# POWER_SUPPLY_CURVE_TRACER_V14.net
KiCad netlist of a schematic drawn in EAGLE
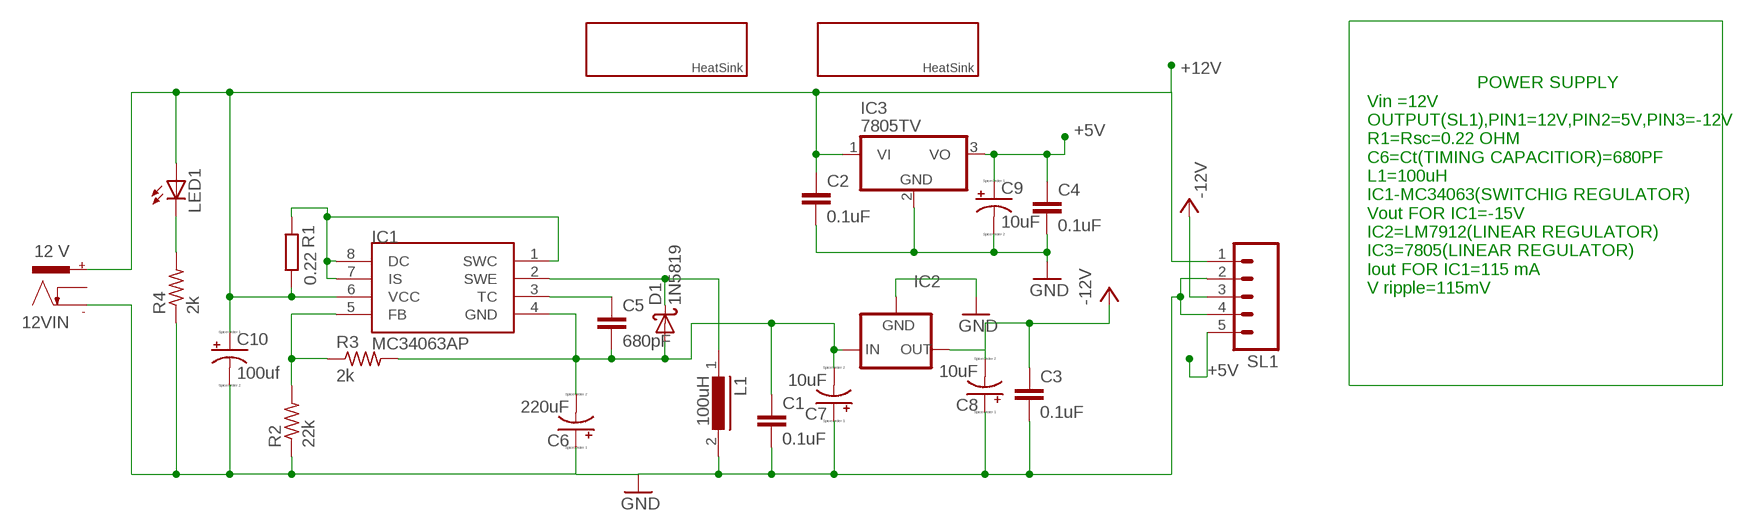
[diagram p0: schematic, sheet 1]

(export (version "E")
  (design (tool "Eeschema 10.0.6"))
  (components
    (comp (ref "12VIN")
      (value "12 V")
      (footprint "eagle-import:NEB21R")
      (libsource (lib "eagle-import") (part "POWER_CON"))
    )
    (comp (ref "C1")
      (value "0.1uF")
      (footprint "eagle-import:C025-025X050")
      (libsource (lib "eagle-import") (part "C-EU025-025X050"))
    )
    (comp (ref "C2")
      (value "0.1uF")
      (footprint "eagle-import:C025-025X050")
      (libsource (lib "eagle-import") (part "C-EU025-025X050"))
    )
    (comp (ref "C3")
      (value "0.1uF")
      (footprint "eagle-import:C025-025X050")
      (libsource (lib "eagle-import") (part "C-EU025-025X050"))
    )
    (comp (ref "C4")
      (value "0.1uF")
      (footprint "eagle-import:C025-025X050")
      (libsource (lib "eagle-import") (part "C-EU025-025X050"))
    )
    (comp (ref "C5")
      (value "680pF")
      (footprint "eagle-import:C025-025X050")
      (libsource (lib "eagle-import") (part "C-EU025-025X050"))
    )
    (comp (ref "C6")
      (value "220uF")
      (footprint "eagle-import:E2,5-7")
      (libsource (lib "eagle-import") (part "CPOL-USE2.5-7"))
    )
    (comp (ref "C7")
      (value "10uF")
      (footprint "eagle-import:E2,5-6")
      (libsource (lib "eagle-import") (part "CPOL-USE2.5-6"))
    )
    (comp (ref "C8")
      (value "10uF")
      (footprint "eagle-import:E2,5-6")
      (libsource (lib "eagle-import") (part "CPOL-USE2.5-6"))
    )
    (comp (ref "C9")
      (value "10uF")
      (footprint "eagle-import:E2,5-6")
      (libsource (lib "eagle-import") (part "CPOL-USE2.5-6"))
    )
    (comp (ref "C10")
      (value "100uf")
      (footprint "eagle-import:E2,5-7")
      (libsource (lib "eagle-import") (part "CPOL-USE2.5-7"))
    )
    (comp (ref "D1")
      (value "1N5819")
      (footprint "eagle-import:DO41-10")
      (libsource (lib "eagle-import") (part "1N5819"))
    )
    (comp (ref "IC1")
      (value "MC34063AP")
      (footprint "eagle-import:DIL08")
      (libsource (lib "eagle-import") (part "MC34063AP"))
    )
    (comp (ref "IC2")
      (value "79XXS")
      (footprint "eagle-import:79XXS")
      (libsource (lib "eagle-import") (part "79XXS"))
    )
    (comp (ref "IC3")
      (value "7805TV")
      (footprint "eagle-import:TO220V")
      (libsource (lib "eagle-import") (part "78TV05"))
    )
    (comp (ref "L1")
      (value "100uH")
      (footprint "eagle-import:82114R")
      (libsource (lib "eagle-import") (part "82114R"))
    )
    (comp (ref "LED1")
      (value "LED3MM")
      (footprint "eagle-import:LED3MM")
      (libsource (lib "eagle-import") (part "LED3MM"))
    )
    (comp (ref "R1")
      (value "0.22")
      (footprint "eagle-import:0617_17")
      (libsource (lib "eagle-import") (part "R-EU_0617/17"))
    )
    (comp (ref "R2")
      (value "22k")
      (footprint "eagle-import:0207_7")
      (libsource (lib "eagle-import") (part "RESISTOR0207/7"))
    )
    (comp (ref "R3")
      (value "2k")
      (footprint "eagle-import:0204_7")
      (libsource (lib "eagle-import") (part "R-US_0204/7"))
    )
    (comp (ref "R4")
      (value "2k")
      (footprint "eagle-import:0207_7")
      (libsource (lib "eagle-import") (part "RESISTOR0207/7"))
    )
    (comp (ref "SL1")
      (value "M05")
      (footprint "eagle-import:05P")
      (libsource (lib "eagle-import") (part "M05"))
    )
    (comp (ref "U$1")
      (value "HEATSINKMEDIUM")
      (footprint "eagle-import:HEATSINK-MED")
      (libsource (lib "eagle-import") (part "HEATSINKMEDIUM"))
    )
    (comp (ref "U$2")
      (value "HEATSINKSMALL")
      (footprint "eagle-import:HEATSINK-SML")
      (libsource (lib "eagle-import") (part "HEATSINKSMALL"))
    )
  )
  (nets
    (net (code "1") (name "-12V") (class "Default")
      (node (ref "C3") (pin "1") (pinfunction "1_1") (pintype "passive"))
      (node (ref "C8") (pin "-") (pinfunction "-_-") (pintype "passive"))
      (node (ref "IC2") (pin "OUT") (pinfunction "OUT_OUT") (pintype "passive"))
      (node (ref "SL1") (pin "3") (pinfunction "3_3") (pintype "passive"))
    )
    (net (code "2") (name "/+5V") (class "Default")
      (node (ref "C4") (pin "1") (pinfunction "1_1") (pintype "passive"))
      (node (ref "C9") (pin "+") (pinfunction "+_+") (pintype "passive"))
      (node (ref "IC3") (pin "3") (pinfunction "VO_3") (pintype "passive"))
      (node (ref "SL1") (pin "5") (pinfunction "5_5") (pintype "passive"))
    )
    (net (code "3") (name "/+12V") (class "Default")
      (node (ref "12VIN") (pin "+") (pinfunction "+_+") (pintype "passive"))
      (node (ref "C10") (pin "+") (pinfunction "+_+") (pintype "passive"))
      (node (ref "C2") (pin "1") (pinfunction "1_1") (pintype "passive"))
      (node (ref "IC1") (pin "6") (pinfunction "VCC_6") (pintype "passive"))
      (node (ref "IC3") (pin "1") (pinfunction "VI_1") (pintype "input"))
      (node (ref "LED1") (pin "A") (pinfunction "A_A") (pintype "passive"))
      (node (ref "R1") (pin "2") (pinfunction "2_2") (pintype "passive"))
      (node (ref "SL1") (pin "1") (pinfunction "1_1") (pintype "passive"))
    )
    (net (code "4") (name "GND") (class "Default")
      (node (ref "12VIN") (pin "-") (pinfunction "-_-") (pintype "passive"))
      (node (ref "C1") (pin "2") (pinfunction "2_2") (pintype "passive"))
      (node (ref "C10") (pin "-") (pinfunction "-_-") (pintype "passive"))
      (node (ref "C2") (pin "2") (pinfunction "2_2") (pintype "passive"))
      (node (ref "C3") (pin "2") (pinfunction "2_2") (pintype "passive"))
      (node (ref "C4") (pin "2") (pinfunction "2_2") (pintype "passive"))
      (node (ref "C6") (pin "+") (pinfunction "+_+") (pintype "passive"))
      (node (ref "C7") (pin "+") (pinfunction "+_+") (pintype "passive"))
      (node (ref "C8") (pin "+") (pinfunction "+_+") (pintype "passive"))
      (node (ref "C9") (pin "-") (pinfunction "-_-") (pintype "passive"))
      (node (ref "IC2") (pin "GND") (pinfunction "GND_GND") (pintype "input"))
      (node (ref "IC3") (pin "2") (pinfunction "GND_2") (pintype "passive"))
      (node (ref "L1") (pin "2") (pinfunction "2_2") (pintype "passive"))
      (node (ref "R2") (pin "1") (pinfunction "1_1") (pintype "passive"))
      (node (ref "R4") (pin "1") (pinfunction "1_1") (pintype "passive"))
      (node (ref "SL1") (pin "2") (pinfunction "2_2") (pintype "passive"))
      (node (ref "SL1") (pin "4") (pinfunction "4_4") (pintype "passive"))
    )
    (net (code "5") (name "Net-(IC1-DC)") (class "Default")
      (node (ref "IC1") (pin "1") (pinfunction "SWC_1") (pintype "passive"))
      (node (ref "IC1") (pin "7") (pinfunction "IS_7") (pintype "passive"))
      (node (ref "IC1") (pin "8") (pinfunction "DC_8") (pintype "passive"))
      (node (ref "R1") (pin "1") (pinfunction "1_1") (pintype "passive"))
    )
    (net (code "6") (name "Net-(IC1-FB)") (class "Default")
      (node (ref "IC1") (pin "5") (pinfunction "FB_5") (pintype "passive"))
      (node (ref "R2") (pin "2") (pinfunction "2_2") (pintype "passive"))
      (node (ref "R3") (pin "1") (pinfunction "1_1") (pintype "passive"))
    )
    (net (code "7") (name "Net-(IC1-GND)") (class "Default")
      (node (ref "C1") (pin "1") (pinfunction "1_1") (pintype "passive"))
      (node (ref "C5") (pin "2") (pinfunction "2_2") (pintype "passive"))
      (node (ref "C6") (pin "-") (pinfunction "-_-") (pintype "passive"))
      (node (ref "C7") (pin "-") (pinfunction "-_-") (pintype "passive"))
      (node (ref "D1") (pin "A") (pinfunction "A_A") (pintype "passive"))
      (node (ref "IC1") (pin "4") (pinfunction "GND_4") (pintype "passive"))
      (node (ref "IC2") (pin "IN") (pinfunction "IN_IN") (pintype "input"))
      (node (ref "R3") (pin "2") (pinfunction "2_2") (pintype "passive"))
    )
    (net (code "8") (name "Net-(IC1-SWE)") (class "Default")
      (node (ref "D1") (pin "C") (pinfunction "C_C") (pintype "passive"))
      (node (ref "IC1") (pin "2") (pinfunction "SWE_2") (pintype "passive"))
      (node (ref "L1") (pin "1") (pinfunction "1_1") (pintype "passive"))
    )
    (net (code "9") (name "Net-(IC1-TC)") (class "Default")
      (node (ref "C5") (pin "1") (pinfunction "1_1") (pintype "passive"))
      (node (ref "IC1") (pin "3") (pinfunction "TC_3") (pintype "passive"))
    )
    (net (code "10") (name "Net-(LED1-C)") (class "Default")
      (node (ref "LED1") (pin "K") (pinfunction "C_K") (pintype "passive"))
      (node (ref "R4") (pin "2") (pinfunction "2_2") (pintype "passive"))
    )
    (net (code "11") (name "unconnected-(12VIN-PadC)") (class "Default")
      (node (ref "12VIN") (pin "C") (pinfunction "C_C") (pintype "passive"))
    )
  )
)
